# schemat.net
KiCad netlist of a schematic drawn in EAGLE
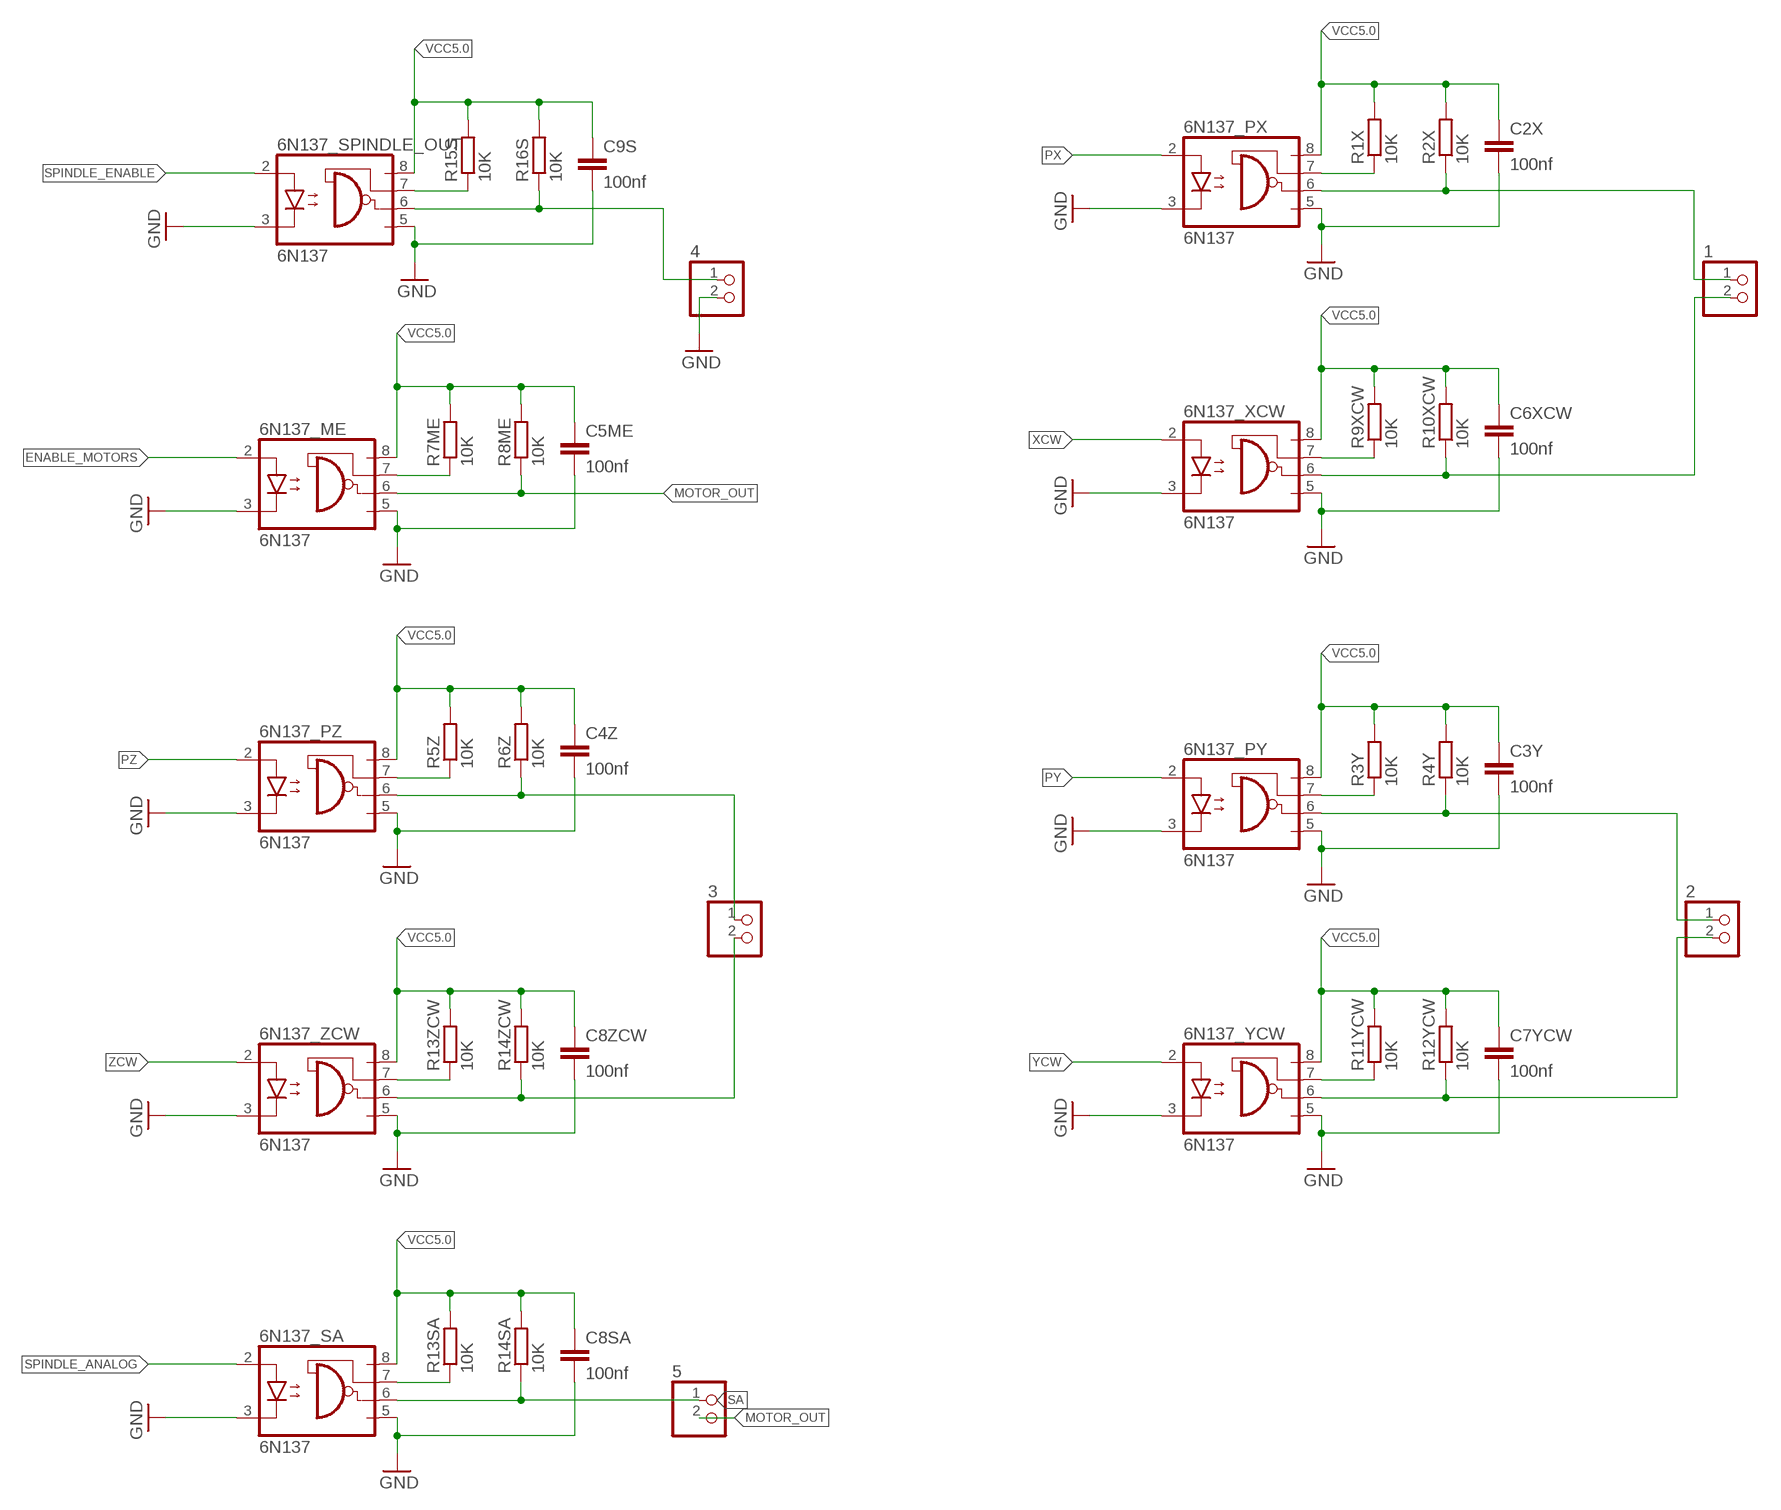
[diagram p0: schematic, sheet 1, part 1 of 2]
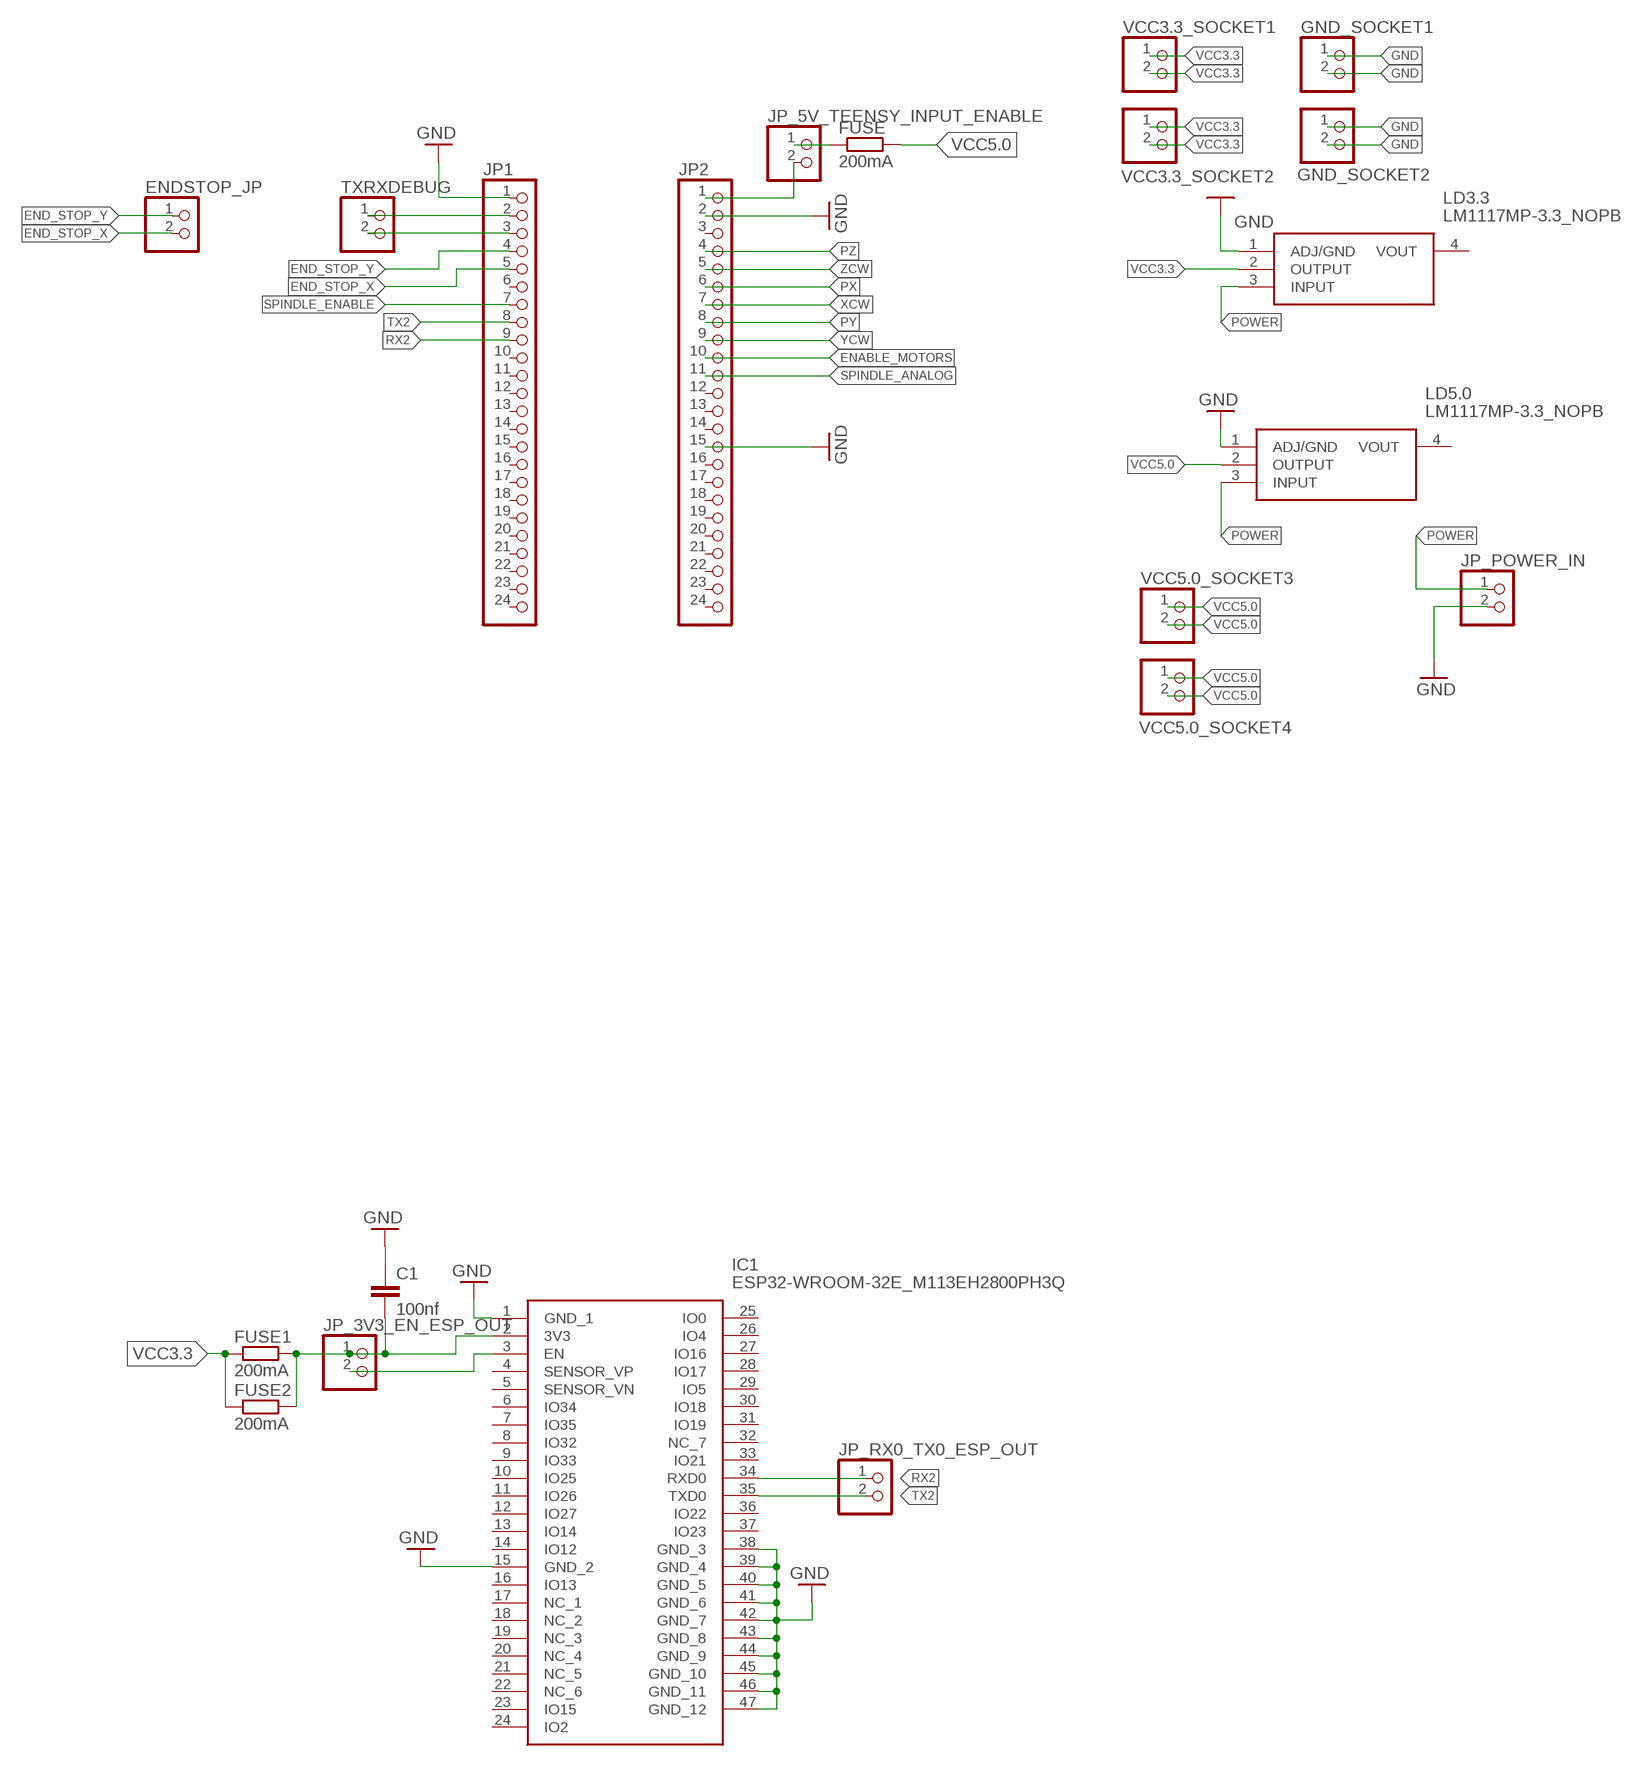
[diagram p1: schematic, sheet 1, part 2 of 2]

(export (version "E")
  (design (tool "Eeschema 10.0.6"))
  (components
    (comp (ref "1")
      (value "PINHD-1X2")
      (footprint "eagle-import:1X02")
      (libsource (lib "eagle-import") (part "PINHD-1X2"))
    )
    (comp (ref "2")
      (value "PINHD-1X2")
      (footprint "eagle-import:1X02")
      (libsource (lib "eagle-import") (part "PINHD-1X2"))
    )
    (comp (ref "3")
      (value "PINHD-1X2")
      (footprint "eagle-import:1X02")
      (libsource (lib "eagle-import") (part "PINHD-1X2"))
    )
    (comp (ref "4")
      (value "PINHD-1X2")
      (footprint "eagle-import:1X02")
      (libsource (lib "eagle-import") (part "PINHD-1X2"))
    )
    (comp (ref "5")
      (value "PINHD-1X2")
      (footprint "eagle-import:1X02")
      (libsource (lib "eagle-import") (part "PINHD-1X2"))
    )
    (comp (ref "6N137_ME")
      (value "6N137")
      (footprint "eagle-import:DIL08")
      (libsource (lib "eagle-import") (part "6N137"))
    )
    (comp (ref "6N137_PX")
      (value "6N137")
      (footprint "eagle-import:DIL08")
      (libsource (lib "eagle-import") (part "6N137"))
    )
    (comp (ref "6N137_PY")
      (value "6N137")
      (footprint "eagle-import:DIL08")
      (libsource (lib "eagle-import") (part "6N137"))
    )
    (comp (ref "6N137_PZ")
      (value "6N137")
      (footprint "eagle-import:DIL08")
      (libsource (lib "eagle-import") (part "6N137"))
    )
    (comp (ref "6N137_SA")
      (value "6N137")
      (footprint "eagle-import:DIL08")
      (libsource (lib "eagle-import") (part "6N137"))
    )
    (comp (ref "6N137_SPINDLE_OUT")
      (value "6N137")
      (footprint "eagle-import:DIL08")
      (libsource (lib "eagle-import") (part "6N137"))
    )
    (comp (ref "6N137_XCW")
      (value "6N137")
      (footprint "eagle-import:DIL08")
      (libsource (lib "eagle-import") (part "6N137"))
    )
    (comp (ref "6N137_YCW")
      (value "6N137")
      (footprint "eagle-import:DIL08")
      (libsource (lib "eagle-import") (part "6N137"))
    )
    (comp (ref "6N137_ZCW")
      (value "6N137")
      (footprint "eagle-import:DIL08")
      (libsource (lib "eagle-import") (part "6N137"))
    )
    (comp (ref "C1")
      (value "100nf")
      (footprint "eagle-import:C0805")
      (libsource (lib "eagle-import") (part "C-EUC0805"))
    )
    (comp (ref "C2X")
      (value "100nf")
      (footprint "eagle-import:C0805")
      (libsource (lib "eagle-import") (part "C-EUC0805"))
    )
    (comp (ref "C3Y")
      (value "100nf")
      (footprint "eagle-import:C0805")
      (libsource (lib "eagle-import") (part "C-EUC0805"))
    )
    (comp (ref "C4Z")
      (value "100nf")
      (footprint "eagle-import:C0805")
      (libsource (lib "eagle-import") (part "C-EUC0805"))
    )
    (comp (ref "C5ME")
      (value "100nf")
      (footprint "eagle-import:C0805")
      (libsource (lib "eagle-import") (part "C-EUC0805"))
    )
    (comp (ref "C6XCW")
      (value "100nf")
      (footprint "eagle-import:C0805")
      (libsource (lib "eagle-import") (part "C-EUC0805"))
    )
    (comp (ref "C7YCW")
      (value "100nf")
      (footprint "eagle-import:C0805")
      (libsource (lib "eagle-import") (part "C-EUC0805"))
    )
    (comp (ref "C8SA")
      (value "100nf")
      (footprint "eagle-import:C0805")
      (libsource (lib "eagle-import") (part "C-EUC0805"))
    )
    (comp (ref "C8ZCW")
      (value "100nf")
      (footprint "eagle-import:C0805")
      (libsource (lib "eagle-import") (part "C-EUC0805"))
    )
    (comp (ref "C9S")
      (value "100nf")
      (footprint "eagle-import:C0805")
      (libsource (lib "eagle-import") (part "C-EUC0805"))
    )
    (comp (ref "ENDSTOP_JP")
      (value "PINHD-1X2")
      (footprint "eagle-import:1X02")
      (libsource (lib "eagle-import") (part "PINHD-1X2"))
    )
    (comp (ref "FUSE")
      (value "200mA")
      (footprint "eagle-import:R2512")
      (libsource (lib "eagle-import") (part "R-EU_R2512"))
    )
    (comp (ref "FUSE1")
      (value "200mA")
      (footprint "eagle-import:R2512")
      (libsource (lib "eagle-import") (part "R-EU_R2512"))
    )
    (comp (ref "FUSE2")
      (value "200mA")
      (footprint "eagle-import:R2512")
      (libsource (lib "eagle-import") (part "R-EU_R2512"))
    )
    (comp (ref "GND_SOCKET1")
      (value "PINHD-1X2")
      (footprint "eagle-import:1X02")
      (libsource (lib "eagle-import") (part "PINHD-1X2"))
    )
    (comp (ref "GND_SOCKET2")
      (value "PINHD-1X2")
      (footprint "eagle-import:1X02")
      (libsource (lib "eagle-import") (part "PINHD-1X2"))
    )
    (comp (ref "IC1")
      (value "ESP32-WROOM-32E_M113EH2800PH3Q")
      (footprint "eagle-import:ESP32WROOM32EM113EH2800PH3Q0")
      (fields
        (field (name "MANUFACTURER_PART_NUMBER") "ESP32-WROOM-32E(M113EH2800PH3Q0)")
        (field (name "MOUSER_PART_NUMBER") "356-ESP32WRM32E128PH")
      )
      (libsource (lib "eagle-import") (part "ESP32-WROOM-32E_M113EH2800PH3Q"))
    )
    (comp (ref "JP1")
      (value "PINHD-1X24")
      (footprint "eagle-import:1X24")
      (libsource (lib "eagle-import") (part "PINHD-1X24"))
    )
    (comp (ref "JP2")
      (value "PINHD-1X24")
      (footprint "eagle-import:1X24")
      (libsource (lib "eagle-import") (part "PINHD-1X24"))
    )
    (comp (ref "JP_3V3_EN_ESP_OUT")
      (value "PINHD-1X2")
      (footprint "eagle-import:1X02")
      (libsource (lib "eagle-import") (part "PINHD-1X2"))
    )
    (comp (ref "JP_5V_TEENSY_INPUT_ENABLE")
      (value "PINHD-1X2")
      (footprint "eagle-import:1X02")
      (libsource (lib "eagle-import") (part "PINHD-1X2"))
    )
    (comp (ref "JP_POWER_IN")
      (value "PINHD-1X2")
      (footprint "eagle-import:1X02")
      (libsource (lib "eagle-import") (part "PINHD-1X2"))
    )
    (comp (ref "JP_RX0_TX0_ESP_OUT")
      (value "PINHD-1X2")
      (footprint "eagle-import:1X02")
      (libsource (lib "eagle-import") (part "PINHD-1X2"))
    )
    (comp (ref "LD3.3")
      (value "LM1117MP-3.3_NOPB")
      (footprint "eagle-import:SOT230P700X180-4N")
      (fields
        (field (name "ARROW_PART_NUMBER") "LM1117MP-3.3/NOPB")
        (field (name "MOUSER_PART_NUMBER") "926-LM1117MP-3.3NOPB")
      )
      (libsource (lib "eagle-import") (part "LM1117MP-3.3_NOPB"))
    )
    (comp (ref "LD5.0")
      (value "LM1117MP-3.3_NOPB")
      (footprint "eagle-import:SOT230P700X180-4N")
      (fields
        (field (name "ARROW_PART_NUMBER") "LM1117MP-3.3/NOPB")
        (field (name "MOUSER_PART_NUMBER") "926-LM1117MP-3.3NOPB")
      )
      (libsource (lib "eagle-import") (part "LM1117MP-3.3_NOPB"))
    )
    (comp (ref "R1X")
      (value "10K")
      (footprint "eagle-import:R0805")
      (libsource (lib "eagle-import") (part "R-EU_R0805"))
    )
    (comp (ref "R2X")
      (value "10K")
      (footprint "eagle-import:R0805")
      (libsource (lib "eagle-import") (part "R-EU_R0805"))
    )
    (comp (ref "R3Y")
      (value "10K")
      (footprint "eagle-import:R0805")
      (libsource (lib "eagle-import") (part "R-EU_R0805"))
    )
    (comp (ref "R4Y")
      (value "10K")
      (footprint "eagle-import:R0805")
      (libsource (lib "eagle-import") (part "R-EU_R0805"))
    )
    (comp (ref "R5Z")
      (value "10K")
      (footprint "eagle-import:R0805")
      (libsource (lib "eagle-import") (part "R-EU_R0805"))
    )
    (comp (ref "R6Z")
      (value "10K")
      (footprint "eagle-import:R0805")
      (libsource (lib "eagle-import") (part "R-EU_R0805"))
    )
    (comp (ref "R7ME")
      (value "10K")
      (footprint "eagle-import:R0805")
      (libsource (lib "eagle-import") (part "R-EU_R0805"))
    )
    (comp (ref "R8ME")
      (value "10K")
      (footprint "eagle-import:R0805")
      (libsource (lib "eagle-import") (part "R-EU_R0805"))
    )
    (comp (ref "R9XCW")
      (value "10K")
      (footprint "eagle-import:R0805")
      (libsource (lib "eagle-import") (part "R-EU_R0805"))
    )
    (comp (ref "R10XCW")
      (value "10K")
      (footprint "eagle-import:R0805")
      (libsource (lib "eagle-import") (part "R-EU_R0805"))
    )
    (comp (ref "R11YCW")
      (value "10K")
      (footprint "eagle-import:R0805")
      (libsource (lib "eagle-import") (part "R-EU_R0805"))
    )
    (comp (ref "R12YCW")
      (value "10K")
      (footprint "eagle-import:R0805")
      (libsource (lib "eagle-import") (part "R-EU_R0805"))
    )
    (comp (ref "R13SA")
      (value "10K")
      (footprint "eagle-import:R0805")
      (libsource (lib "eagle-import") (part "R-EU_R0805"))
    )
    (comp (ref "R13ZCW")
      (value "10K")
      (footprint "eagle-import:R0805")
      (libsource (lib "eagle-import") (part "R-EU_R0805"))
    )
    (comp (ref "R14SA")
      (value "10K")
      (footprint "eagle-import:R0805")
      (libsource (lib "eagle-import") (part "R-EU_R0805"))
    )
    (comp (ref "R14ZCW")
      (value "10K")
      (footprint "eagle-import:R0805")
      (libsource (lib "eagle-import") (part "R-EU_R0805"))
    )
    (comp (ref "R15S")
      (value "10K")
      (footprint "eagle-import:R0805")
      (libsource (lib "eagle-import") (part "R-EU_R0805"))
    )
    (comp (ref "R16S")
      (value "10K")
      (footprint "eagle-import:R0805")
      (libsource (lib "eagle-import") (part "R-EU_R0805"))
    )
    (comp (ref "TXRXDEBUG")
      (value "PINHD-1X2")
      (footprint "eagle-import:1X02")
      (libsource (lib "eagle-import") (part "PINHD-1X2"))
    )
    (comp (ref "VCC3.3_SOCKET1")
      (value "PINHD-1X2")
      (footprint "eagle-import:1X02")
      (libsource (lib "eagle-import") (part "PINHD-1X2"))
    )
    (comp (ref "VCC3.3_SOCKET2")
      (value "PINHD-1X2")
      (footprint "eagle-import:1X02")
      (libsource (lib "eagle-import") (part "PINHD-1X2"))
    )
    (comp (ref "VCC5.0_SOCKET3")
      (value "PINHD-1X2")
      (footprint "eagle-import:1X02")
      (libsource (lib "eagle-import") (part "PINHD-1X2"))
    )
    (comp (ref "VCC5.0_SOCKET4")
      (value "PINHD-1X2")
      (footprint "eagle-import:1X02")
      (libsource (lib "eagle-import") (part "PINHD-1X2"))
    )
  )
  (nets
    (net (code "1") (name "ENABLE_MOTORS") (class "Default")
      (node (ref "6N137_ME") (pin "2") (pinfunction "A_2") (pintype "passive"))
      (node (ref "JP2") (pin "10") (pinfunction "10_10") (pintype "passive"))
    )
    (net (code "2") (name "END_STOP_X") (class "Default")
      (node (ref "ENDSTOP_JP") (pin "2") (pinfunction "2_2") (pintype "passive"))
      (node (ref "JP1") (pin "5") (pinfunction "5_5") (pintype "passive"))
    )
    (net (code "3") (name "END_STOP_Y") (class "Default")
      (node (ref "ENDSTOP_JP") (pin "1") (pinfunction "1_1") (pintype "passive"))
      (node (ref "JP1") (pin "4") (pinfunction "4_4") (pintype "passive"))
    )
    (net (code "4") (name "GND") (class "Default")
      (node (ref "4") (pin "2") (pinfunction "2_2") (pintype "passive"))
      (node (ref "6N137_ME") (pin "3") (pinfunction "C_3") (pintype "passive"))
      (node (ref "6N137_ME") (pin "5") (pinfunction "GND_5") (pintype "passive"))
      (node (ref "6N137_PX") (pin "3") (pinfunction "C_3") (pintype "passive"))
      (node (ref "6N137_PX") (pin "5") (pinfunction "GND_5") (pintype "passive"))
      (node (ref "6N137_PY") (pin "3") (pinfunction "C_3") (pintype "passive"))
      (node (ref "6N137_PY") (pin "5") (pinfunction "GND_5") (pintype "passive"))
      (node (ref "6N137_PZ") (pin "3") (pinfunction "C_3") (pintype "passive"))
      (node (ref "6N137_PZ") (pin "5") (pinfunction "GND_5") (pintype "passive"))
      (node (ref "6N137_SA") (pin "3") (pinfunction "C_3") (pintype "passive"))
      (node (ref "6N137_SA") (pin "5") (pinfunction "GND_5") (pintype "passive"))
      (node (ref "6N137_SPINDLE_OUT") (pin "3") (pinfunction "C_3") (pintype "passive"))
      (node (ref "6N137_SPINDLE_OUT") (pin "5") (pinfunction "GND_5") (pintype "passive"))
      (node (ref "6N137_XCW") (pin "3") (pinfunction "C_3") (pintype "passive"))
      (node (ref "6N137_XCW") (pin "5") (pinfunction "GND_5") (pintype "passive"))
      (node (ref "6N137_YCW") (pin "3") (pinfunction "C_3") (pintype "passive"))
      (node (ref "6N137_YCW") (pin "5") (pinfunction "GND_5") (pintype "passive"))
      (node (ref "6N137_ZCW") (pin "3") (pinfunction "C_3") (pintype "passive"))
      (node (ref "6N137_ZCW") (pin "5") (pinfunction "GND_5") (pintype "passive"))
      (node (ref "C1") (pin "1") (pinfunction "1_1") (pintype "passive"))
      (node (ref "C2X") (pin "2") (pinfunction "2_2") (pintype "passive"))
      (node (ref "C3Y") (pin "2") (pinfunction "2_2") (pintype "passive"))
      (node (ref "C4Z") (pin "2") (pinfunction "2_2") (pintype "passive"))
      (node (ref "C5ME") (pin "2") (pinfunction "2_2") (pintype "passive"))
      (node (ref "C6XCW") (pin "2") (pinfunction "2_2") (pintype "passive"))
      (node (ref "C7YCW") (pin "2") (pinfunction "2_2") (pintype "passive"))
      (node (ref "C8SA") (pin "2") (pinfunction "2_2") (pintype "passive"))
      (node (ref "C8ZCW") (pin "2") (pinfunction "2_2") (pintype "passive"))
      (node (ref "C9S") (pin "2") (pinfunction "2_2") (pintype "passive"))
      (node (ref "GND_SOCKET1") (pin "1") (pinfunction "1_1") (pintype "passive"))
      (node (ref "GND_SOCKET1") (pin "2") (pinfunction "2_2") (pintype "passive"))
      (node (ref "GND_SOCKET2") (pin "1") (pinfunction "1_1") (pintype "passive"))
      (node (ref "GND_SOCKET2") (pin "2") (pinfunction "2_2") (pintype "passive"))
      (node (ref "IC1") (pin "1") (pinfunction "GND_1_1") (pintype "bidirectional"))
      (node (ref "IC1") (pin "15") (pinfunction "GND_2_15") (pintype "bidirectional"))
      (node (ref "IC1") (pin "38") (pinfunction "GND_3_38") (pintype "bidirectional"))
      (node (ref "IC1") (pin "39") (pinfunction "GND_4_39") (pintype "bidirectional"))
      (node (ref "IC1") (pin "40") (pinfunction "GND_5_40") (pintype "bidirectional"))
      (node (ref "IC1") (pin "41") (pinfunction "GND_6_41") (pintype "bidirectional"))
      (node (ref "IC1") (pin "42") (pinfunction "GND_7_42") (pintype "bidirectional"))
      (node (ref "IC1") (pin "43") (pinfunction "GND_8_43") (pintype "bidirectional"))
      (node (ref "IC1") (pin "44") (pinfunction "GND_9_44") (pintype "bidirectional"))
      (node (ref "IC1") (pin "45") (pinfunction "GND_10_45") (pintype "bidirectional"))
      (node (ref "IC1") (pin "46") (pinfunction "GND_11_46") (pintype "bidirectional"))
      (node (ref "IC1") (pin "47") (pinfunction "GND_12_47") (pintype "bidirectional"))
      (node (ref "JP1") (pin "1") (pinfunction "1_1") (pintype "passive"))
      (node (ref "JP2") (pin "15") (pinfunction "15_15") (pintype "passive"))
      (node (ref "JP2") (pin "2") (pinfunction "2_2") (pintype "passive"))
      (node (ref "JP_POWER_IN") (pin "2") (pinfunction "2_2") (pintype "passive"))
      (node (ref "LD3.3") (pin "1") (pinfunction "ADJ/GND_1") (pintype "bidirectional"))
      (node (ref "LD5.0") (pin "1") (pinfunction "ADJ/GND_1") (pintype "bidirectional"))
    )
    (net (code "5") (name "MOTOR_OUT") (class "Default")
      (node (ref "5") (pin "2") (pinfunction "2_2") (pintype "passive"))
      (node (ref "6N137_ME") (pin "6") (pinfunction "VO_6") (pintype "passive"))
      (node (ref "R8ME") (pin "1") (pinfunction "1_1") (pintype "passive"))
    )
    (net (code "6") (name "Net-(6N137_ME-VE)") (class "Default")
      (node (ref "6N137_ME") (pin "7") (pinfunction "VE_7") (pintype "passive"))
      (node (ref "R7ME") (pin "1") (pinfunction "1_1") (pintype "passive"))
    )
    (net (code "7") (name "Net-(6N137_PX-VE)") (class "Default")
      (node (ref "6N137_PX") (pin "7") (pinfunction "VE_7") (pintype "passive"))
      (node (ref "R1X") (pin "1") (pinfunction "1_1") (pintype "passive"))
    )
    (net (code "8") (name "Net-(6N137_PX-VO)") (class "Default")
      (node (ref "1") (pin "1") (pinfunction "1_1") (pintype "passive"))
      (node (ref "6N137_PX") (pin "6") (pinfunction "VO_6") (pintype "passive"))
      (node (ref "R2X") (pin "1") (pinfunction "1_1") (pintype "passive"))
    )
    (net (code "9") (name "Net-(6N137_PY-VE)") (class "Default")
      (node (ref "6N137_PY") (pin "7") (pinfunction "VE_7") (pintype "passive"))
      (node (ref "R3Y") (pin "1") (pinfunction "1_1") (pintype "passive"))
    )
    (net (code "10") (name "Net-(6N137_PY-VO)") (class "Default")
      (node (ref "2") (pin "1") (pinfunction "1_1") (pintype "passive"))
      (node (ref "6N137_PY") (pin "6") (pinfunction "VO_6") (pintype "passive"))
      (node (ref "R4Y") (pin "1") (pinfunction "1_1") (pintype "passive"))
    )
    (net (code "11") (name "Net-(6N137_PZ-VE)") (class "Default")
      (node (ref "6N137_PZ") (pin "7") (pinfunction "VE_7") (pintype "passive"))
      (node (ref "R5Z") (pin "1") (pinfunction "1_1") (pintype "passive"))
    )
    (net (code "12") (name "Net-(6N137_PZ-VO)") (class "Default")
      (node (ref "3") (pin "1") (pinfunction "1_1") (pintype "passive"))
      (node (ref "6N137_PZ") (pin "6") (pinfunction "VO_6") (pintype "passive"))
      (node (ref "R6Z") (pin "1") (pinfunction "1_1") (pintype "passive"))
    )
    (net (code "13") (name "Net-(6N137_SA-VE)") (class "Default")
      (node (ref "6N137_SA") (pin "7") (pinfunction "VE_7") (pintype "passive"))
      (node (ref "R13SA") (pin "1") (pinfunction "1_1") (pintype "passive"))
    )
    (net (code "14") (name "Net-(6N137_SPINDLE_OUT-VE)") (class "Default")
      (node (ref "6N137_SPINDLE_OUT") (pin "7") (pinfunction "VE_7") (pintype "passive"))
      (node (ref "R15S") (pin "1") (pinfunction "1_1") (pintype "passive"))
    )
    (net (code "15") (name "Net-(6N137_SPINDLE_OUT-VO)") (class "Default")
      (node (ref "4") (pin "1") (pinfunction "1_1") (pintype "passive"))
      (node (ref "6N137_SPINDLE_OUT") (pin "6") (pinfunction "VO_6") (pintype "passive"))
      (node (ref "R16S") (pin "1") (pinfunction "1_1") (pintype "passive"))
    )
    (net (code "16") (name "Net-(6N137_XCW-VE)") (class "Default")
      (node (ref "6N137_XCW") (pin "7") (pinfunction "VE_7") (pintype "passive"))
      (node (ref "R9XCW") (pin "1") (pinfunction "1_1") (pintype "passive"))
    )
    (net (code "17") (name "Net-(6N137_XCW-VO)") (class "Default")
      (node (ref "1") (pin "2") (pinfunction "2_2") (pintype "passive"))
      (node (ref "6N137_XCW") (pin "6") (pinfunction "VO_6") (pintype "passive"))
      (node (ref "R10XCW") (pin "1") (pinfunction "1_1") (pintype "passive"))
    )
    (net (code "18") (name "Net-(6N137_YCW-VE)") (class "Default")
      (node (ref "6N137_YCW") (pin "7") (pinfunction "VE_7") (pintype "passive"))
      (node (ref "R11YCW") (pin "1") (pinfunction "1_1") (pintype "passive"))
    )
    (net (code "19") (name "Net-(6N137_YCW-VO)") (class "Default")
      (node (ref "2") (pin "2") (pinfunction "2_2") (pintype "passive"))
      (node (ref "6N137_YCW") (pin "6") (pinfunction "VO_6") (pintype "passive"))
      (node (ref "R12YCW") (pin "1") (pinfunction "1_1") (pintype "passive"))
    )
    (net (code "20") (name "Net-(6N137_ZCW-VE)") (class "Default")
      (node (ref "6N137_ZCW") (pin "7") (pinfunction "VE_7") (pintype "passive"))
      (node (ref "R13ZCW") (pin "1") (pinfunction "1_1") (pintype "passive"))
    )
    (net (code "21") (name "Net-(6N137_ZCW-VO)") (class "Default")
      (node (ref "3") (pin "2") (pinfunction "2_2") (pintype "passive"))
      (node (ref "6N137_ZCW") (pin "6") (pinfunction "VO_6") (pintype "passive"))
      (node (ref "R14ZCW") (pin "1") (pinfunction "1_1") (pintype "passive"))
    )
    (net (code "22") (name "Net-(FUSE-Pad1)") (class "Default")
      (node (ref "FUSE") (pin "1") (pinfunction "1_1") (pintype "passive"))
      (node (ref "JP_5V_TEENSY_INPUT_ENABLE") (pin "1") (pinfunction "1_1") (pintype "passive"))
    )
    (net (code "23") (name "Net-(IC1-3V3)") (class "Default")
      (node (ref "C1") (pin "2") (pinfunction "2_2") (pintype "passive"))
      (node (ref "FUSE1") (pin "2") (pinfunction "2_2") (pintype "passive"))
      (node (ref "FUSE2") (pin "2") (pinfunction "2_2") (pintype "passive"))
      (node (ref "IC1") (pin "2") (pinfunction "3V3_2") (pintype "bidirectional"))
      (node (ref "JP_3V3_EN_ESP_OUT") (pin "1") (pinfunction "1_1") (pintype "passive"))
    )
    (net (code "24") (name "Net-(IC1-EN)") (class "Default")
      (node (ref "IC1") (pin "3") (pinfunction "EN_3") (pintype "bidirectional"))
      (node (ref "JP_3V3_EN_ESP_OUT") (pin "2") (pinfunction "2_2") (pintype "passive"))
    )
    (net (code "25") (name "Net-(JP1-Pad2)") (class "Default")
      (node (ref "JP1") (pin "2") (pinfunction "2_2") (pintype "passive"))
      (node (ref "TXRXDEBUG") (pin "1") (pinfunction "1_1") (pintype "passive"))
    )
    (net (code "26") (name "Net-(JP1-Pad3)") (class "Default")
      (node (ref "JP1") (pin "3") (pinfunction "3_3") (pintype "passive"))
      (node (ref "TXRXDEBUG") (pin "2") (pinfunction "2_2") (pintype "passive"))
    )
    (net (code "27") (name "Net-(JP2-Pad1)") (class "Default")
      (node (ref "JP2") (pin "1") (pinfunction "1_1") (pintype "passive"))
      (node (ref "JP_5V_TEENSY_INPUT_ENABLE") (pin "2") (pinfunction "2_2") (pintype "passive"))
    )
    (net (code "28") (name "POWER") (class "Default")
      (node (ref "JP_POWER_IN") (pin "1") (pinfunction "1_1") (pintype "passive"))
      (node (ref "LD3.3") (pin "3") (pinfunction "INPUT_3") (pintype "bidirectional"))
      (node (ref "LD5.0") (pin "3") (pinfunction "INPUT_3") (pintype "bidirectional"))
    )
    (net (code "29") (name "PX") (class "Default")
      (node (ref "6N137_PX") (pin "2") (pinfunction "A_2") (pintype "passive"))
      (node (ref "JP2") (pin "6") (pinfunction "6_6") (pintype "passive"))
    )
    (net (code "30") (name "PY") (class "Default")
      (node (ref "6N137_PY") (pin "2") (pinfunction "A_2") (pintype "passive"))
      (node (ref "JP2") (pin "8") (pinfunction "8_8") (pintype "passive"))
    )
    (net (code "31") (name "PZ") (class "Default")
      (node (ref "6N137_PZ") (pin "2") (pinfunction "A_2") (pintype "passive"))
      (node (ref "JP2") (pin "4") (pinfunction "4_4") (pintype "passive"))
    )
    (net (code "32") (name "RX2") (class "Default")
      (node (ref "IC1") (pin "34") (pinfunction "RXD0_34") (pintype "bidirectional"))
      (node (ref "JP1") (pin "9") (pinfunction "9_9") (pintype "passive"))
      (node (ref "JP_RX0_TX0_ESP_OUT") (pin "1") (pinfunction "1_1") (pintype "passive"))
    )
    (net (code "33") (name "SA") (class "Default")
      (node (ref "5") (pin "1") (pinfunction "1_1") (pintype "passive"))
      (node (ref "6N137_SA") (pin "6") (pinfunction "VO_6") (pintype "passive"))
      (node (ref "R14SA") (pin "1") (pinfunction "1_1") (pintype "passive"))
    )
    (net (code "34") (name "SPINDLE_ANALOG") (class "Default")
      (node (ref "6N137_SA") (pin "2") (pinfunction "A_2") (pintype "passive"))
      (node (ref "JP2") (pin "11") (pinfunction "11_11") (pintype "passive"))
    )
    (net (code "35") (name "SPINDLE_ENABLE") (class "Default")
      (node (ref "6N137_SPINDLE_OUT") (pin "2") (pinfunction "A_2") (pintype "passive"))
      (node (ref "JP1") (pin "7") (pinfunction "7_7") (pintype "passive"))
    )
    (net (code "36") (name "TX2") (class "Default")
      (node (ref "IC1") (pin "35") (pinfunction "TXD0_35") (pintype "bidirectional"))
      (node (ref "JP1") (pin "8") (pinfunction "8_8") (pintype "passive"))
      (node (ref "JP_RX0_TX0_ESP_OUT") (pin "2") (pinfunction "2_2") (pintype "passive"))
    )
    (net (code "37") (name "VCC3.3") (class "Default")
      (node (ref "FUSE1") (pin "1") (pinfunction "1_1") (pintype "passive"))
      (node (ref "FUSE2") (pin "1") (pinfunction "1_1") (pintype "passive"))
      (node (ref "LD3.3") (pin "2") (pinfunction "OUTPUT_2") (pintype "bidirectional"))
      (node (ref "VCC3.3_SOCKET1") (pin "1") (pinfunction "1_1") (pintype "passive"))
      (node (ref "VCC3.3_SOCKET1") (pin "2") (pinfunction "2_2") (pintype "passive"))
      (node (ref "VCC3.3_SOCKET2") (pin "1") (pinfunction "1_1") (pintype "passive"))
      (node (ref "VCC3.3_SOCKET2") (pin "2") (pinfunction "2_2") (pintype "passive"))
    )
    (net (code "38") (name "VCC5.0") (class "Default")
      (node (ref "6N137_ME") (pin "8") (pinfunction "VCC_8") (pintype "passive"))
      (node (ref "6N137_PX") (pin "8") (pinfunction "VCC_8") (pintype "passive"))
      (node (ref "6N137_PY") (pin "8") (pinfunction "VCC_8") (pintype "passive"))
      (node (ref "6N137_PZ") (pin "8") (pinfunction "VCC_8") (pintype "passive"))
      (node (ref "6N137_SA") (pin "8") (pinfunction "VCC_8") (pintype "passive"))
      (node (ref "6N137_SPINDLE_OUT") (pin "8") (pinfunction "VCC_8") (pintype "passive"))
      (node (ref "6N137_XCW") (pin "8") (pinfunction "VCC_8") (pintype "passive"))
      (node (ref "6N137_YCW") (pin "8") (pinfunction "VCC_8") (pintype "passive"))
      (node (ref "6N137_ZCW") (pin "8") (pinfunction "VCC_8") (pintype "passive"))
      (node (ref "C2X") (pin "1") (pinfunction "1_1") (pintype "passive"))
      (node (ref "C3Y") (pin "1") (pinfunction "1_1") (pintype "passive"))
      (node (ref "C4Z") (pin "1") (pinfunction "1_1") (pintype "passive"))
      (node (ref "C5ME") (pin "1") (pinfunction "1_1") (pintype "passive"))
      (node (ref "C6XCW") (pin "1") (pinfunction "1_1") (pintype "passive"))
      (node (ref "C7YCW") (pin "1") (pinfunction "1_1") (pintype "passive"))
      (node (ref "C8SA") (pin "1") (pinfunction "1_1") (pintype "passive"))
      (node (ref "C8ZCW") (pin "1") (pinfunction "1_1") (pintype "passive"))
      (node (ref "C9S") (pin "1") (pinfunction "1_1") (pintype "passive"))
      (node (ref "FUSE") (pin "2") (pinfunction "2_2") (pintype "passive"))
      (node (ref "LD5.0") (pin "2") (pinfunction "OUTPUT_2") (pintype "bidirectional"))
      (node (ref "R10XCW") (pin "2") (pinfunction "2_2") (pintype "passive"))
      (node (ref "R11YCW") (pin "2") (pinfunction "2_2") (pintype "passive"))
      (node (ref "R12YCW") (pin "2") (pinfunction "2_2") (pintype "passive"))
      (node (ref "R13SA") (pin "2") (pinfunction "2_2") (pintype "passive"))
      (node (ref "R13ZCW") (pin "2") (pinfunction "2_2") (pintype "passive"))
      (node (ref "R14SA") (pin "2") (pinfunction "2_2") (pintype "passive"))
      (node (ref "R14ZCW") (pin "2") (pinfunction "2_2") (pintype "passive"))
      (node (ref "R15S") (pin "2") (pinfunction "2_2") (pintype "passive"))
      (node (ref "R16S") (pin "2") (pinfunction "2_2") (pintype "passive"))
      (node (ref "R1X") (pin "2") (pinfunction "2_2") (pintype "passive"))
      (node (ref "R2X") (pin "2") (pinfunction "2_2") (pintype "passive"))
      (node (ref "R3Y") (pin "2") (pinfunction "2_2") (pintype "passive"))
      (node (ref "R4Y") (pin "2") (pinfunction "2_2") (pintype "passive"))
      (node (ref "R5Z") (pin "2") (pinfunction "2_2") (pintype "passive"))
      (node (ref "R6Z") (pin "2") (pinfunction "2_2") (pintype "passive"))
      (node (ref "R7ME") (pin "2") (pinfunction "2_2") (pintype "passive"))
      (node (ref "R8ME") (pin "2") (pinfunction "2_2") (pintype "passive"))
      (node (ref "R9XCW") (pin "2") (pinfunction "2_2") (pintype "passive"))
      (node (ref "VCC5.0_SOCKET3") (pin "1") (pinfunction "1_1") (pintype "passive"))
      (node (ref "VCC5.0_SOCKET3") (pin "2") (pinfunction "2_2") (pintype "passive"))
      (node (ref "VCC5.0_SOCKET4") (pin "1") (pinfunction "1_1") (pintype "passive"))
      (node (ref "VCC5.0_SOCKET4") (pin "2") (pinfunction "2_2") (pintype "passive"))
    )
    (net (code "39") (name "XCW") (class "Default")
      (node (ref "6N137_XCW") (pin "2") (pinfunction "A_2") (pintype "passive"))
      (node (ref "JP2") (pin "7") (pinfunction "7_7") (pintype "passive"))
    )
    (net (code "40") (name "YCW") (class "Default")
      (node (ref "6N137_YCW") (pin "2") (pinfunction "A_2") (pintype "passive"))
      (node (ref "JP2") (pin "9") (pinfunction "9_9") (pintype "passive"))
    )
    (net (code "41") (name "ZCW") (class "Default")
      (node (ref "6N137_ZCW") (pin "2") (pinfunction "A_2") (pintype "passive"))
      (node (ref "JP2") (pin "5") (pinfunction "5_5") (pintype "passive"))
    )
    (net (code "42") (name "unconnected-(IC1-IO0-Pad25)") (class "Default")
      (node (ref "IC1") (pin "25") (pinfunction "IO0_25") (pintype "bidirectional"))
    )
    (net (code "43") (name "unconnected-(IC1-IO2-Pad24)") (class "Default")
      (node (ref "IC1") (pin "24") (pinfunction "IO2_24") (pintype "bidirectional"))
    )
    (net (code "44") (name "unconnected-(IC1-IO4-Pad26)") (class "Default")
      (node (ref "IC1") (pin "26") (pinfunction "IO4_26") (pintype "bidirectional"))
    )
    (net (code "45") (name "unconnected-(IC1-IO5-Pad29)") (class "Default")
      (node (ref "IC1") (pin "29") (pinfunction "IO5_29") (pintype "bidirectional"))
    )
    (net (code "46") (name "unconnected-(IC1-IO12-Pad14)") (class "Default")
      (node (ref "IC1") (pin "14") (pinfunction "IO12_14") (pintype "bidirectional"))
    )
    (net (code "47") (name "unconnected-(IC1-IO13-Pad16)") (class "Default")
      (node (ref "IC1") (pin "16") (pinfunction "IO13_16") (pintype "bidirectional"))
    )
    (net (code "48") (name "unconnected-(IC1-IO14-Pad13)") (class "Default")
      (node (ref "IC1") (pin "13") (pinfunction "IO14_13") (pintype "bidirectional"))
    )
    (net (code "49") (name "unconnected-(IC1-IO15-Pad23)") (class "Default")
      (node (ref "IC1") (pin "23") (pinfunction "IO15_23") (pintype "bidirectional"))
    )
    (net (code "50") (name "unconnected-(IC1-IO16-Pad27)") (class "Default")
      (node (ref "IC1") (pin "27") (pinfunction "IO16_27") (pintype "bidirectional"))
    )
    (net (code "51") (name "unconnected-(IC1-IO17-Pad28)") (class "Default")
      (node (ref "IC1") (pin "28") (pinfunction "IO17_28") (pintype "bidirectional"))
    )
    (net (code "52") (name "unconnected-(IC1-IO18-Pad30)") (class "Default")
      (node (ref "IC1") (pin "30") (pinfunction "IO18_30") (pintype "bidirectional"))
    )
    (net (code "53") (name "unconnected-(IC1-IO19-Pad31)") (class "Default")
      (node (ref "IC1") (pin "31") (pinfunction "IO19_31") (pintype "bidirectional"))
    )
    (net (code "54") (name "unconnected-(IC1-IO21-Pad33)") (class "Default")
      (node (ref "IC1") (pin "33") (pinfunction "IO21_33") (pintype "bidirectional"))
    )
    (net (code "55") (name "unconnected-(IC1-IO22-Pad36)") (class "Default")
      (node (ref "IC1") (pin "36") (pinfunction "IO22_36") (pintype "bidirectional"))
    )
    (net (code "56") (name "unconnected-(IC1-IO23-Pad37)") (class "Default")
      (node (ref "IC1") (pin "37") (pinfunction "IO23_37") (pintype "bidirectional"))
    )
    (net (code "57") (name "unconnected-(IC1-IO25-Pad10)") (class "Default")
      (node (ref "IC1") (pin "10") (pinfunction "IO25_10") (pintype "bidirectional"))
    )
    (net (code "58") (name "unconnected-(IC1-IO26-Pad11)") (class "Default")
      (node (ref "IC1") (pin "11") (pinfunction "IO26_11") (pintype "bidirectional"))
    )
    (net (code "59") (name "unconnected-(IC1-IO27-Pad12)") (class "Default")
      (node (ref "IC1") (pin "12") (pinfunction "IO27_12") (pintype "bidirectional"))
    )
    (net (code "60") (name "unconnected-(IC1-IO32-Pad8)") (class "Default")
      (node (ref "IC1") (pin "8") (pinfunction "IO32_8") (pintype "bidirectional"))
    )
    (net (code "61") (name "unconnected-(IC1-IO33-Pad9)") (class "Default")
      (node (ref "IC1") (pin "9") (pinfunction "IO33_9") (pintype "bidirectional"))
    )
    (net (code "62") (name "unconnected-(IC1-IO34-Pad6)") (class "Default")
      (node (ref "IC1") (pin "6") (pinfunction "IO34_6") (pintype "bidirectional"))
    )
    (net (code "63") (name "unconnected-(IC1-IO35-Pad7)") (class "Default")
      (node (ref "IC1") (pin "7") (pinfunction "IO35_7") (pintype "bidirectional"))
    )
    (net (code "64") (name "unconnected-(IC1-NC_1-Pad17)") (class "Default")
      (node (ref "IC1") (pin "17") (pinfunction "NC_1_17") (pintype "bidirectional"))
    )
    (net (code "65") (name "unconnected-(IC1-NC_2-Pad18)") (class "Default")
      (node (ref "IC1") (pin "18") (pinfunction "NC_2_18") (pintype "bidirectional"))
    )
    (net (code "66") (name "unconnected-(IC1-NC_3-Pad19)") (class "Default")
      (node (ref "IC1") (pin "19") (pinfunction "NC_3_19") (pintype "bidirectional"))
    )
    (net (code "67") (name "unconnected-(IC1-NC_4-Pad20)") (class "Default")
      (node (ref "IC1") (pin "20") (pinfunction "NC_4_20") (pintype "bidirectional"))
    )
    (net (code "68") (name "unconnected-(IC1-NC_5-Pad21)") (class "Default")
      (node (ref "IC1") (pin "21") (pinfunction "NC_5_21") (pintype "bidirectional"))
    )
    (net (code "69") (name "unconnected-(IC1-NC_6-Pad22)") (class "Default")
      (node (ref "IC1") (pin "22") (pinfunction "NC_6_22") (pintype "bidirectional"))
    )
    (net (code "70") (name "unconnected-(IC1-NC_7-Pad32)") (class "Default")
      (node (ref "IC1") (pin "32") (pinfunction "NC_7_32") (pintype "bidirectional"))
    )
    (net (code "71") (name "unconnected-(IC1-SENSOR_VN-Pad5)") (class "Default")
      (node (ref "IC1") (pin "5") (pinfunction "SENSOR_VN_5") (pintype "bidirectional"))
    )
    (net (code "72") (name "unconnected-(IC1-SENSOR_VP-Pad4)") (class "Default")
      (node (ref "IC1") (pin "4") (pinfunction "SENSOR_VP_4") (pintype "bidirectional"))
    )
    (net (code "73") (name "unconnected-(JP1-Pad6)") (class "Default")
      (node (ref "JP1") (pin "6") (pinfunction "6_6") (pintype "passive"))
    )
    (net (code "74") (name "unconnected-(JP1-Pad10)") (class "Default")
      (node (ref "JP1") (pin "10") (pinfunction "10_10") (pintype "passive"))
    )
    (net (code "75") (name "unconnected-(JP1-Pad11)") (class "Default")
      (node (ref "JP1") (pin "11") (pinfunction "11_11") (pintype "passive"))
    )
    (net (code "76") (name "unconnected-(JP1-Pad12)") (class "Default")
      (node (ref "JP1") (pin "12") (pinfunction "12_12") (pintype "passive"))
    )
    (net (code "77") (name "unconnected-(JP1-Pad13)") (class "Default")
      (node (ref "JP1") (pin "13") (pinfunction "13_13") (pintype "passive"))
    )
    (net (code "78") (name "unconnected-(JP1-Pad14)") (class "Default")
      (node (ref "JP1") (pin "14") (pinfunction "14_14") (pintype "passive"))
    )
    (net (code "79") (name "unconnected-(JP1-Pad15)") (class "Default")
      (node (ref "JP1") (pin "15") (pinfunction "15_15") (pintype "passive"))
    )
    (net (code "80") (name "unconnected-(JP1-Pad16)") (class "Default")
      (node (ref "JP1") (pin "16") (pinfunction "16_16") (pintype "passive"))
    )
    (net (code "81") (name "unconnected-(JP1-Pad17)") (class "Default")
      (node (ref "JP1") (pin "17") (pinfunction "17_17") (pintype "passive"))
    )
    (net (code "82") (name "unconnected-(JP1-Pad18)") (class "Default")
      (node (ref "JP1") (pin "18") (pinfunction "18_18") (pintype "passive"))
    )
    (net (code "83") (name "unconnected-(JP1-Pad19)") (class "Default")
      (node (ref "JP1") (pin "19") (pinfunction "19_19") (pintype "passive"))
    )
    (net (code "84") (name "unconnected-(JP1-Pad20)") (class "Default")
      (node (ref "JP1") (pin "20") (pinfunction "20_20") (pintype "passive"))
    )
    (net (code "85") (name "unconnected-(JP1-Pad21)") (class "Default")
      (node (ref "JP1") (pin "21") (pinfunction "21_21") (pintype "passive"))
    )
    (net (code "86") (name "unconnected-(JP1-Pad22)") (class "Default")
      (node (ref "JP1") (pin "22") (pinfunction "22_22") (pintype "passive"))
    )
    (net (code "87") (name "unconnected-(JP1-Pad23)") (class "Default")
      (node (ref "JP1") (pin "23") (pinfunction "23_23") (pintype "passive"))
    )
    (net (code "88") (name "unconnected-(JP1-Pad24)") (class "Default")
      (node (ref "JP1") (pin "24") (pinfunction "24_24") (pintype "passive"))
    )
    (net (code "89") (name "unconnected-(JP2-Pad3)") (class "Default")
      (node (ref "JP2") (pin "3") (pinfunction "3_3") (pintype "passive"))
    )
    (net (code "90") (name "unconnected-(JP2-Pad12)") (class "Default")
      (node (ref "JP2") (pin "12") (pinfunction "12_12") (pintype "passive"))
    )
    (net (code "91") (name "unconnected-(JP2-Pad13)") (class "Default")
      (node (ref "JP2") (pin "13") (pinfunction "13_13") (pintype "passive"))
    )
    (net (code "92") (name "unconnected-(JP2-Pad14)") (class "Default")
      (node (ref "JP2") (pin "14") (pinfunction "14_14") (pintype "passive"))
    )
    (net (code "93") (name "unconnected-(JP2-Pad16)") (class "Default")
      (node (ref "JP2") (pin "16") (pinfunction "16_16") (pintype "passive"))
    )
    (net (code "94") (name "unconnected-(JP2-Pad17)") (class "Default")
      (node (ref "JP2") (pin "17") (pinfunction "17_17") (pintype "passive"))
    )
    (net (code "95") (name "unconnected-(JP2-Pad18)") (class "Default")
      (node (ref "JP2") (pin "18") (pinfunction "18_18") (pintype "passive"))
    )
    (net (code "96") (name "unconnected-(JP2-Pad19)") (class "Default")
      (node (ref "JP2") (pin "19") (pinfunction "19_19") (pintype "passive"))
    )
    (net (code "97") (name "unconnected-(JP2-Pad20)") (class "Default")
      (node (ref "JP2") (pin "20") (pinfunction "20_20") (pintype "passive"))
    )
    (net (code "98") (name "unconnected-(JP2-Pad21)") (class "Default")
      (node (ref "JP2") (pin "21") (pinfunction "21_21") (pintype "passive"))
    )
    (net (code "99") (name "unconnected-(JP2-Pad22)") (class "Default")
      (node (ref "JP2") (pin "22") (pinfunction "22_22") (pintype "passive"))
    )
    (net (code "100") (name "unconnected-(JP2-Pad23)") (class "Default")
      (node (ref "JP2") (pin "23") (pinfunction "23_23") (pintype "passive"))
    )
    (net (code "101") (name "unconnected-(JP2-Pad24)") (class "Default")
      (node (ref "JP2") (pin "24") (pinfunction "24_24") (pintype "passive"))
    )
    (net (code "102") (name "unconnected-(LD3.3-VOUT-Pad4)") (class "Default")
      (node (ref "LD3.3") (pin "4") (pinfunction "VOUT_4") (pintype "bidirectional"))
    )
    (net (code "103") (name "unconnected-(LD5.0-VOUT-Pad4)") (class "Default")
      (node (ref "LD5.0") (pin "4") (pinfunction "VOUT_4") (pintype "bidirectional"))
    )
  )
)
